# lcd.net
KiCad netlist of a schematic drawn in EAGLE
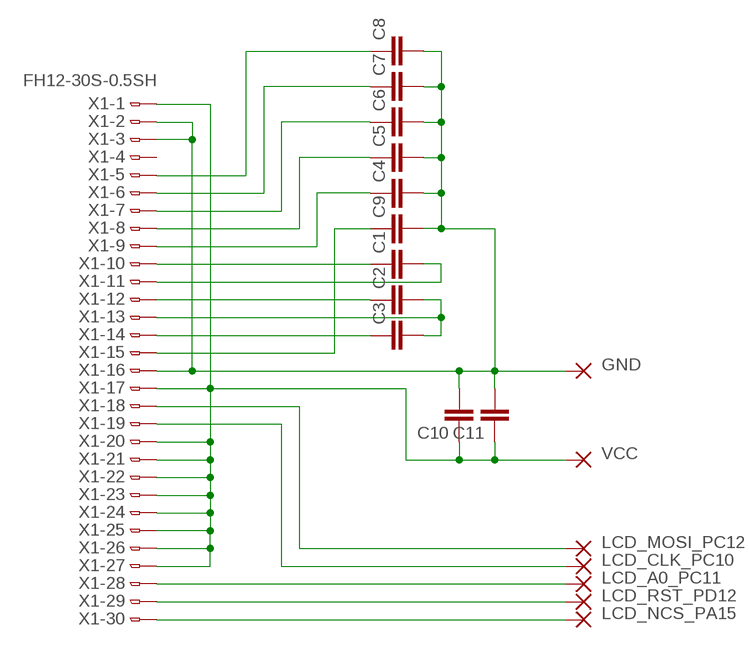
[diagram p0: schematic, sheet 1]

(export (version "E")
  (design (tool "Eeschema 10.0.6"))
  (components
    (comp (ref "C1")
      (value "C-EUC0805")
      (footprint "eagle-import:C0805")
      (libsource (lib "eagle-import") (part "C-EUC0805"))
    )
    (comp (ref "C2")
      (value "C-EUC0805")
      (footprint "eagle-import:C0805")
      (libsource (lib "eagle-import") (part "C-EUC0805"))
    )
    (comp (ref "C3")
      (value "C-EUC0805")
      (footprint "eagle-import:C0805")
      (libsource (lib "eagle-import") (part "C-EUC0805"))
    )
    (comp (ref "C4")
      (value "C-EUC0805")
      (footprint "eagle-import:C0805")
      (libsource (lib "eagle-import") (part "C-EUC0805"))
    )
    (comp (ref "C5")
      (value "C-EUC0805")
      (footprint "eagle-import:C0805")
      (libsource (lib "eagle-import") (part "C-EUC0805"))
    )
    (comp (ref "C6")
      (value "C-EUC0805")
      (footprint "eagle-import:C0805")
      (libsource (lib "eagle-import") (part "C-EUC0805"))
    )
    (comp (ref "C7")
      (value "C-EUC0805")
      (footprint "eagle-import:C0805")
      (libsource (lib "eagle-import") (part "C-EUC0805"))
    )
    (comp (ref "C8")
      (value "C-EUC0805")
      (footprint "eagle-import:C0805")
      (libsource (lib "eagle-import") (part "C-EUC0805"))
    )
    (comp (ref "C9")
      (value "C-EUC0805")
      (footprint "eagle-import:C0805")
      (libsource (lib "eagle-import") (part "C-EUC0805"))
    )
    (comp (ref "C10")
      (value "C-EUC0805")
      (footprint "eagle-import:C0805")
      (libsource (lib "eagle-import") (part "C-EUC0805"))
    )
    (comp (ref "C11")
      (value "C-EUC0805")
      (footprint "eagle-import:C0805")
      (libsource (lib "eagle-import") (part "C-EUC0805"))
    )
    (comp (ref "PAD1")
      (value "WIREPADSMD5-2,5")
      (footprint "eagle-import:5-2,5")
      (libsource (lib "eagle-import") (part "WIREPADSMD5-2,5"))
    )
    (comp (ref "PAD2")
      (value "WIREPADSMD5-2,5")
      (footprint "eagle-import:5-2,5")
      (libsource (lib "eagle-import") (part "WIREPADSMD5-2,5"))
    )
    (comp (ref "PAD3")
      (value "WIREPADSMD5-2,5")
      (footprint "eagle-import:5-2,5")
      (libsource (lib "eagle-import") (part "WIREPADSMD5-2,5"))
    )
    (comp (ref "PAD4")
      (value "WIREPADSMD5-2,5")
      (footprint "eagle-import:5-2,5")
      (libsource (lib "eagle-import") (part "WIREPADSMD5-2,5"))
    )
    (comp (ref "PAD5")
      (value "WIREPADSMD5-2,5")
      (footprint "eagle-import:5-2,5")
      (libsource (lib "eagle-import") (part "WIREPADSMD5-2,5"))
    )
    (comp (ref "PAD6")
      (value "WIREPADSMD5-2,5")
      (footprint "eagle-import:5-2,5")
      (libsource (lib "eagle-import") (part "WIREPADSMD5-2,5"))
    )
    (comp (ref "PAD7")
      (value "WIREPADSMD5-2,5")
      (footprint "eagle-import:5-2,5")
      (libsource (lib "eagle-import") (part "WIREPADSMD5-2,5"))
    )
    (comp (ref "X1")
      (value "FH12-30S-0.5SH")
      (footprint "eagle-import:FH12-30S-0.5SH")
      (fields (field (name "MPN") "FH12-30S-0.5SH(55)"))
      (libsource (lib "eagle-import") (part "FH12-30S-0.5SH"))
    )
  )
  (nets
    (net (code "1") (name "/GND") (class "Default")
      (node (ref "C10") (pin "2") (pinfunction "2_2") (pintype "passive"))
      (node (ref "C11") (pin "2") (pinfunction "2_2") (pintype "passive"))
      (node (ref "C4") (pin "2") (pinfunction "2_2") (pintype "passive"))
      (node (ref "C5") (pin "2") (pinfunction "2_2") (pintype "passive"))
      (node (ref "C6") (pin "2") (pinfunction "2_2") (pintype "passive"))
      (node (ref "C7") (pin "2") (pinfunction "2_2") (pintype "passive"))
      (node (ref "C8") (pin "2") (pinfunction "2_2") (pintype "passive"))
      (node (ref "C9") (pin "2") (pinfunction "2_2") (pintype "passive"))
      (node (ref "PAD6") (pin "1") (pinfunction "P_1") (pintype "passive"))
      (node (ref "X1") (pin "16") (pinfunction "1_16") (pintype "passive"))
      (node (ref "X1") (pin "2") (pinfunction "1_2") (pintype "passive"))
      (node (ref "X1") (pin "3") (pinfunction "1_3") (pintype "passive"))
    )
    (net (code "2") (name "/LCD_A0_PC11") (class "Default")
      (node (ref "PAD3") (pin "1") (pinfunction "P_1") (pintype "passive"))
      (node (ref "X1") (pin "28") (pinfunction "1_28") (pintype "passive"))
    )
    (net (code "3") (name "/LCD_CLK_PC10") (class "Default")
      (node (ref "PAD2") (pin "1") (pinfunction "P_1") (pintype "passive"))
      (node (ref "X1") (pin "19") (pinfunction "1_19") (pintype "passive"))
    )
    (net (code "4") (name "/LCD_MOSI_PC12") (class "Default")
      (node (ref "PAD1") (pin "1") (pinfunction "P_1") (pintype "passive"))
      (node (ref "X1") (pin "18") (pinfunction "1_18") (pintype "passive"))
    )
    (net (code "5") (name "/LCD_NCS_PA15") (class "Default")
      (node (ref "PAD5") (pin "1") (pinfunction "P_1") (pintype "passive"))
      (node (ref "X1") (pin "30") (pinfunction "1_30") (pintype "passive"))
    )
    (net (code "6") (name "/LCD_RST_PD12") (class "Default")
      (node (ref "PAD4") (pin "1") (pinfunction "P_1") (pintype "passive"))
      (node (ref "X1") (pin "29") (pinfunction "1_29") (pintype "passive"))
    )
    (net (code "7") (name "/VCC") (class "Default")
      (node (ref "C10") (pin "1") (pinfunction "1_1") (pintype "passive"))
      (node (ref "C11") (pin "1") (pinfunction "1_1") (pintype "passive"))
      (node (ref "PAD7") (pin "1") (pinfunction "P_1") (pintype "passive"))
      (node (ref "X1") (pin "1") (pinfunction "1_1") (pintype "passive"))
      (node (ref "X1") (pin "17") (pinfunction "1_17") (pintype "passive"))
      (node (ref "X1") (pin "20") (pinfunction "1_20") (pintype "passive"))
      (node (ref "X1") (pin "21") (pinfunction "1_21") (pintype "passive"))
      (node (ref "X1") (pin "22") (pinfunction "1_22") (pintype "passive"))
      (node (ref "X1") (pin "23") (pinfunction "1_23") (pintype "passive"))
      (node (ref "X1") (pin "24") (pinfunction "1_24") (pintype "passive"))
      (node (ref "X1") (pin "25") (pinfunction "1_25") (pintype "passive"))
      (node (ref "X1") (pin "26") (pinfunction "1_26") (pintype "passive"))
      (node (ref "X1") (pin "27") (pinfunction "1_27") (pintype "passive"))
    )
    (net (code "8") (name "Net-(X1AA-1)") (class "Default")
      (node (ref "C7") (pin "1") (pinfunction "1_1") (pintype "passive"))
      (node (ref "X1") (pin "6") (pinfunction "1_6") (pintype "passive"))
    )
    (net (code "9") (name "Net-(X1AB-1)") (class "Default")
      (node (ref "C6") (pin "1") (pinfunction "1_1") (pintype "passive"))
      (node (ref "X1") (pin "7") (pinfunction "1_7") (pintype "passive"))
    )
    (net (code "10") (name "Net-(X1AC-1)") (class "Default")
      (node (ref "C5") (pin "1") (pinfunction "1_1") (pintype "passive"))
      (node (ref "X1") (pin "8") (pinfunction "1_8") (pintype "passive"))
    )
    (net (code "11") (name "Net-(X1AD-1)") (class "Default")
      (node (ref "C4") (pin "1") (pinfunction "1_1") (pintype "passive"))
      (node (ref "X1") (pin "9") (pinfunction "1_9") (pintype "passive"))
    )
    (net (code "12") (name "Net-(X1B-1)") (class "Default")
      (node (ref "C1") (pin "1") (pinfunction "1_1") (pintype "passive"))
      (node (ref "X1") (pin "10") (pinfunction "1_10") (pintype "passive"))
    )
    (net (code "13") (name "Net-(X1C-1)") (class "Default")
      (node (ref "C1") (pin "2") (pinfunction "2_2") (pintype "passive"))
      (node (ref "X1") (pin "11") (pinfunction "1_11") (pintype "passive"))
    )
    (net (code "14") (name "Net-(X1D-1)") (class "Default")
      (node (ref "C2") (pin "1") (pinfunction "1_1") (pintype "passive"))
      (node (ref "X1") (pin "12") (pinfunction "1_12") (pintype "passive"))
    )
    (net (code "15") (name "Net-(X1E-1)") (class "Default")
      (node (ref "C2") (pin "2") (pinfunction "2_2") (pintype "passive"))
      (node (ref "C3") (pin "2") (pinfunction "2_2") (pintype "passive"))
      (node (ref "X1") (pin "13") (pinfunction "1_13") (pintype "passive"))
    )
    (net (code "16") (name "Net-(X1F-1)") (class "Default")
      (node (ref "C3") (pin "1") (pinfunction "1_1") (pintype "passive"))
      (node (ref "X1") (pin "14") (pinfunction "1_14") (pintype "passive"))
    )
    (net (code "17") (name "Net-(X1G-1)") (class "Default")
      (node (ref "C9") (pin "1") (pinfunction "1_1") (pintype "passive"))
      (node (ref "X1") (pin "15") (pinfunction "1_15") (pintype "passive"))
    )
    (net (code "18") (name "Net-(X1Z-1)") (class "Default")
      (node (ref "C8") (pin "1") (pinfunction "1_1") (pintype "passive"))
      (node (ref "X1") (pin "5") (pinfunction "1_5") (pintype "passive"))
    )
    (net (code "19") (name "unconnected-(X1Y-1-Pad4)") (class "Default")
      (node (ref "X1") (pin "4") (pinfunction "1_4") (pintype "passive"))
    )
  )
)
